# led_button_board.net
KiCad netlist of a schematic drawn in EAGLE
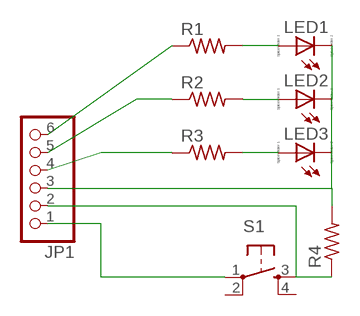
[diagram p0: schematic, sheet 1]

(export (version "E")
  (design (tool "Eeschema 10.0.6"))
  (components
    (comp (ref "JP1")
      (value "PINHD-1X6")
      (footprint "eagle-import:1X06")
      (libsource (lib "eagle-import") (part "PINHD-1X6"))
    )
    (comp (ref "LED1")
      (value "LED_E")
      (footprint "eagle-import:LED_1206")
      (libsource (lib "eagle-import") (part "LED_E"))
    )
    (comp (ref "LED2")
      (value "LED_E")
      (footprint "eagle-import:LED_1206")
      (libsource (lib "eagle-import") (part "LED_E"))
    )
    (comp (ref "LED3")
      (value "LED_E")
      (footprint "eagle-import:LED_1206")
      (libsource (lib "eagle-import") (part "LED_E"))
    )
    (comp (ref "R1")
      (value "RES-US1206FAB")
      (footprint "eagle-import:R1206FAB")
      (libsource (lib "eagle-import") (part "RES-US1206FAB"))
    )
    (comp (ref "R2")
      (value "RES-US1206FAB")
      (footprint "eagle-import:R1206FAB")
      (libsource (lib "eagle-import") (part "RES-US1206FAB"))
    )
    (comp (ref "R3")
      (value "RES-US1206FAB")
      (footprint "eagle-import:R1206FAB")
      (libsource (lib "eagle-import") (part "RES-US1206FAB"))
    )
    (comp (ref "R4")
      (value "RES-US1206")
      (footprint "eagle-import:R1206")
      (libsource (lib "eagle-import") (part "RES-US1206"))
    )
    (comp (ref "S1")
      (value "6MM_SWITCH6MM_SWITCH")
      (footprint "eagle-import:6MM_SWITCH")
      (libsource (lib "eagle-import") (part "6MM_SWITCH6MM_SWITCH"))
    )
  )
  (nets
    (net (code "1") (name "Net-(JP1-Pad3)") (class "Default")
      (node (ref "JP1") (pin "3") (pinfunction "3_3") (pintype "passive"))
      (node (ref "LED1") (pin "C") (pinfunction "C_C") (pintype "passive"))
      (node (ref "LED2") (pin "C") (pinfunction "C_C") (pintype "passive"))
      (node (ref "LED3") (pin "C") (pinfunction "C_C") (pintype "passive"))
      (node (ref "R4") (pin "2") (pinfunction "2_2") (pintype "passive"))
    )
    (net (code "2") (name "Net-(JP1-Pad4)") (class "Default")
      (node (ref "JP1") (pin "4") (pinfunction "4_4") (pintype "passive"))
      (node (ref "R3") (pin "1") (pinfunction "1_1") (pintype "passive"))
    )
    (net (code "3") (name "Net-(JP1-Pad5)") (class "Default")
      (node (ref "JP1") (pin "5") (pinfunction "5_5") (pintype "passive"))
      (node (ref "R2") (pin "1") (pinfunction "1_1") (pintype "passive"))
    )
    (net (code "4") (name "Net-(JP1-Pad6)") (class "Default")
      (node (ref "JP1") (pin "6") (pinfunction "6_6") (pintype "passive"))
      (node (ref "R1") (pin "1") (pinfunction "1_1") (pintype "passive"))
    )
    (net (code "5") (name "Net-(LED1-PadA)") (class "Default")
      (node (ref "LED1") (pin "A") (pinfunction "A_A") (pintype "passive"))
      (node (ref "R1") (pin "2") (pinfunction "2_2") (pintype "passive"))
    )
    (net (code "6") (name "Net-(LED2-PadA)") (class "Default")
      (node (ref "LED2") (pin "A") (pinfunction "A_A") (pintype "passive"))
      (node (ref "R2") (pin "2") (pinfunction "2_2") (pintype "passive"))
    )
    (net (code "7") (name "Net-(LED3-PadA)") (class "Default")
      (node (ref "LED3") (pin "A") (pinfunction "A_A") (pintype "passive"))
      (node (ref "R3") (pin "2") (pinfunction "2_2") (pintype "passive"))
    )
    (net (code "8") (name "Net-(S1-P)") (class "Default")
      (node (ref "JP1") (pin "1") (pinfunction "1_1") (pintype "passive"))
      (node (ref "S1") (pin "1") (pinfunction "P_1") (pintype "passive"))
    )
    (net (code "9") (name "Net-(S1-S)") (class "Default")
      (node (ref "JP1") (pin "2") (pinfunction "2_2") (pintype "passive"))
      (node (ref "R4") (pin "1") (pinfunction "1_1") (pintype "passive"))
      (node (ref "S1") (pin "3") (pinfunction "S_3") (pintype "passive"))
    )
    (net (code "10") (name "unconnected-(S1-P1-Pad2)") (class "Default")
      (node (ref "S1") (pin "2") (pinfunction "P1_2") (pintype "passive"))
    )
    (net (code "11") (name "unconnected-(S1-S1-Pad4)") (class "Default")
      (node (ref "S1") (pin "4") (pinfunction "S1_4") (pintype "passive"))
    )
  )
)
